# Barrido_de_par_metros_y_Trasiente.net
KiCad netlist of a schematic drawn in Altium Designer
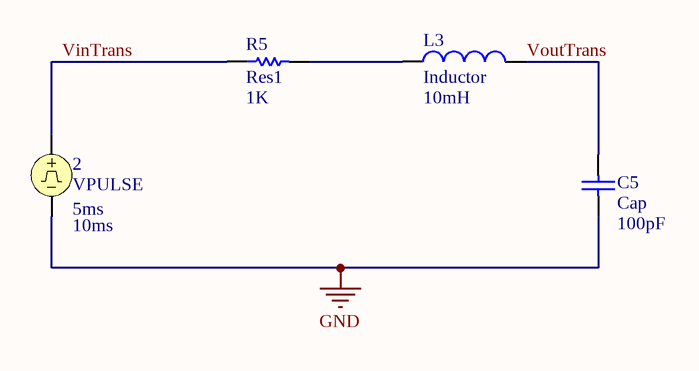
[diagram p0: Barrido de parámetros y Trasiente.SchDoc]

(export (version "E")
  (design (tool "Eeschema 10.0.6"))
  (components
    (comp (ref "2")
      (value "VPULSE")
      (description "Pulse Voltage Source")
      (fields
        (field (name "PULSE WIDTH") "5ms")
        (field (name "PERIOD") "10ms")
        (field (name "PUBLISHER") "Altium Limited")
      )
      (libsource (lib "Simulation Sources") (part "VPULSE"))
    )
    (comp (ref "C5")
      (value "Cap")
      (footprint "RAD-0.3")
      (description "Capacitor")
      (fields (field (name "ALTIUM_VALUE") "100pF") (field (name "PUBLISHER") "Altium Limited"))
      (libsource (lib "Miscellaneous Devices") (part "Cap"))
    )
    (comp (ref "L3")
      (value "Inductor")
      (footprint "0402-A")
      (fields (field (name "ALTIUM_VALUE") "10mH") (field (name "PUBLISHER") "Altium Limited"))
      (libsource (lib "Miscellaneous Devices") (part "Inductor"))
    )
    (comp (ref "R5")
      (value "Res1")
      (footprint "AXIAL-0.3")
      (description "Resistor")
      (fields (field (name "ALTIUM_VALUE") "1K") (field (name "PUBLISHER") "Altium Limited"))
      (libsource (lib "Miscellaneous Devices") (part "Res1"))
    )
  )
  (nets
    (net (code "1") (name "/VinTrans") (class "Default")
      (node (ref "2") (pin "1") (pinfunction "1_1") (pintype "passive"))
      (node (ref "R5") (pin "1") (pinfunction "1_1") (pintype "passive"))
    )
    (net (code "2") (name "/VoutTrans") (class "Default")
      (node (ref "C5") (pin "2") (pinfunction "2_2") (pintype "passive"))
      (node (ref "L3") (pin "2") (pinfunction "2_2") (pintype "passive"))
    )
    (net (code "3") (name "GND") (class "Default")
      (node (ref "2") (pin "2") (pinfunction "2_2") (pintype "passive"))
      (node (ref "C5") (pin "1") (pinfunction "1_1") (pintype "passive"))
    )
    (net (code "4") (name "Net-(L3-Pad1)") (class "Default")
      (node (ref "L3") (pin "1") (pinfunction "1_1") (pintype "passive"))
      (node (ref "R5") (pin "2") (pinfunction "2_2") (pintype "passive"))
    )
  )
)
